# sensortag_motherboard_v005.net
KiCad netlist of a schematic drawn in EAGLE
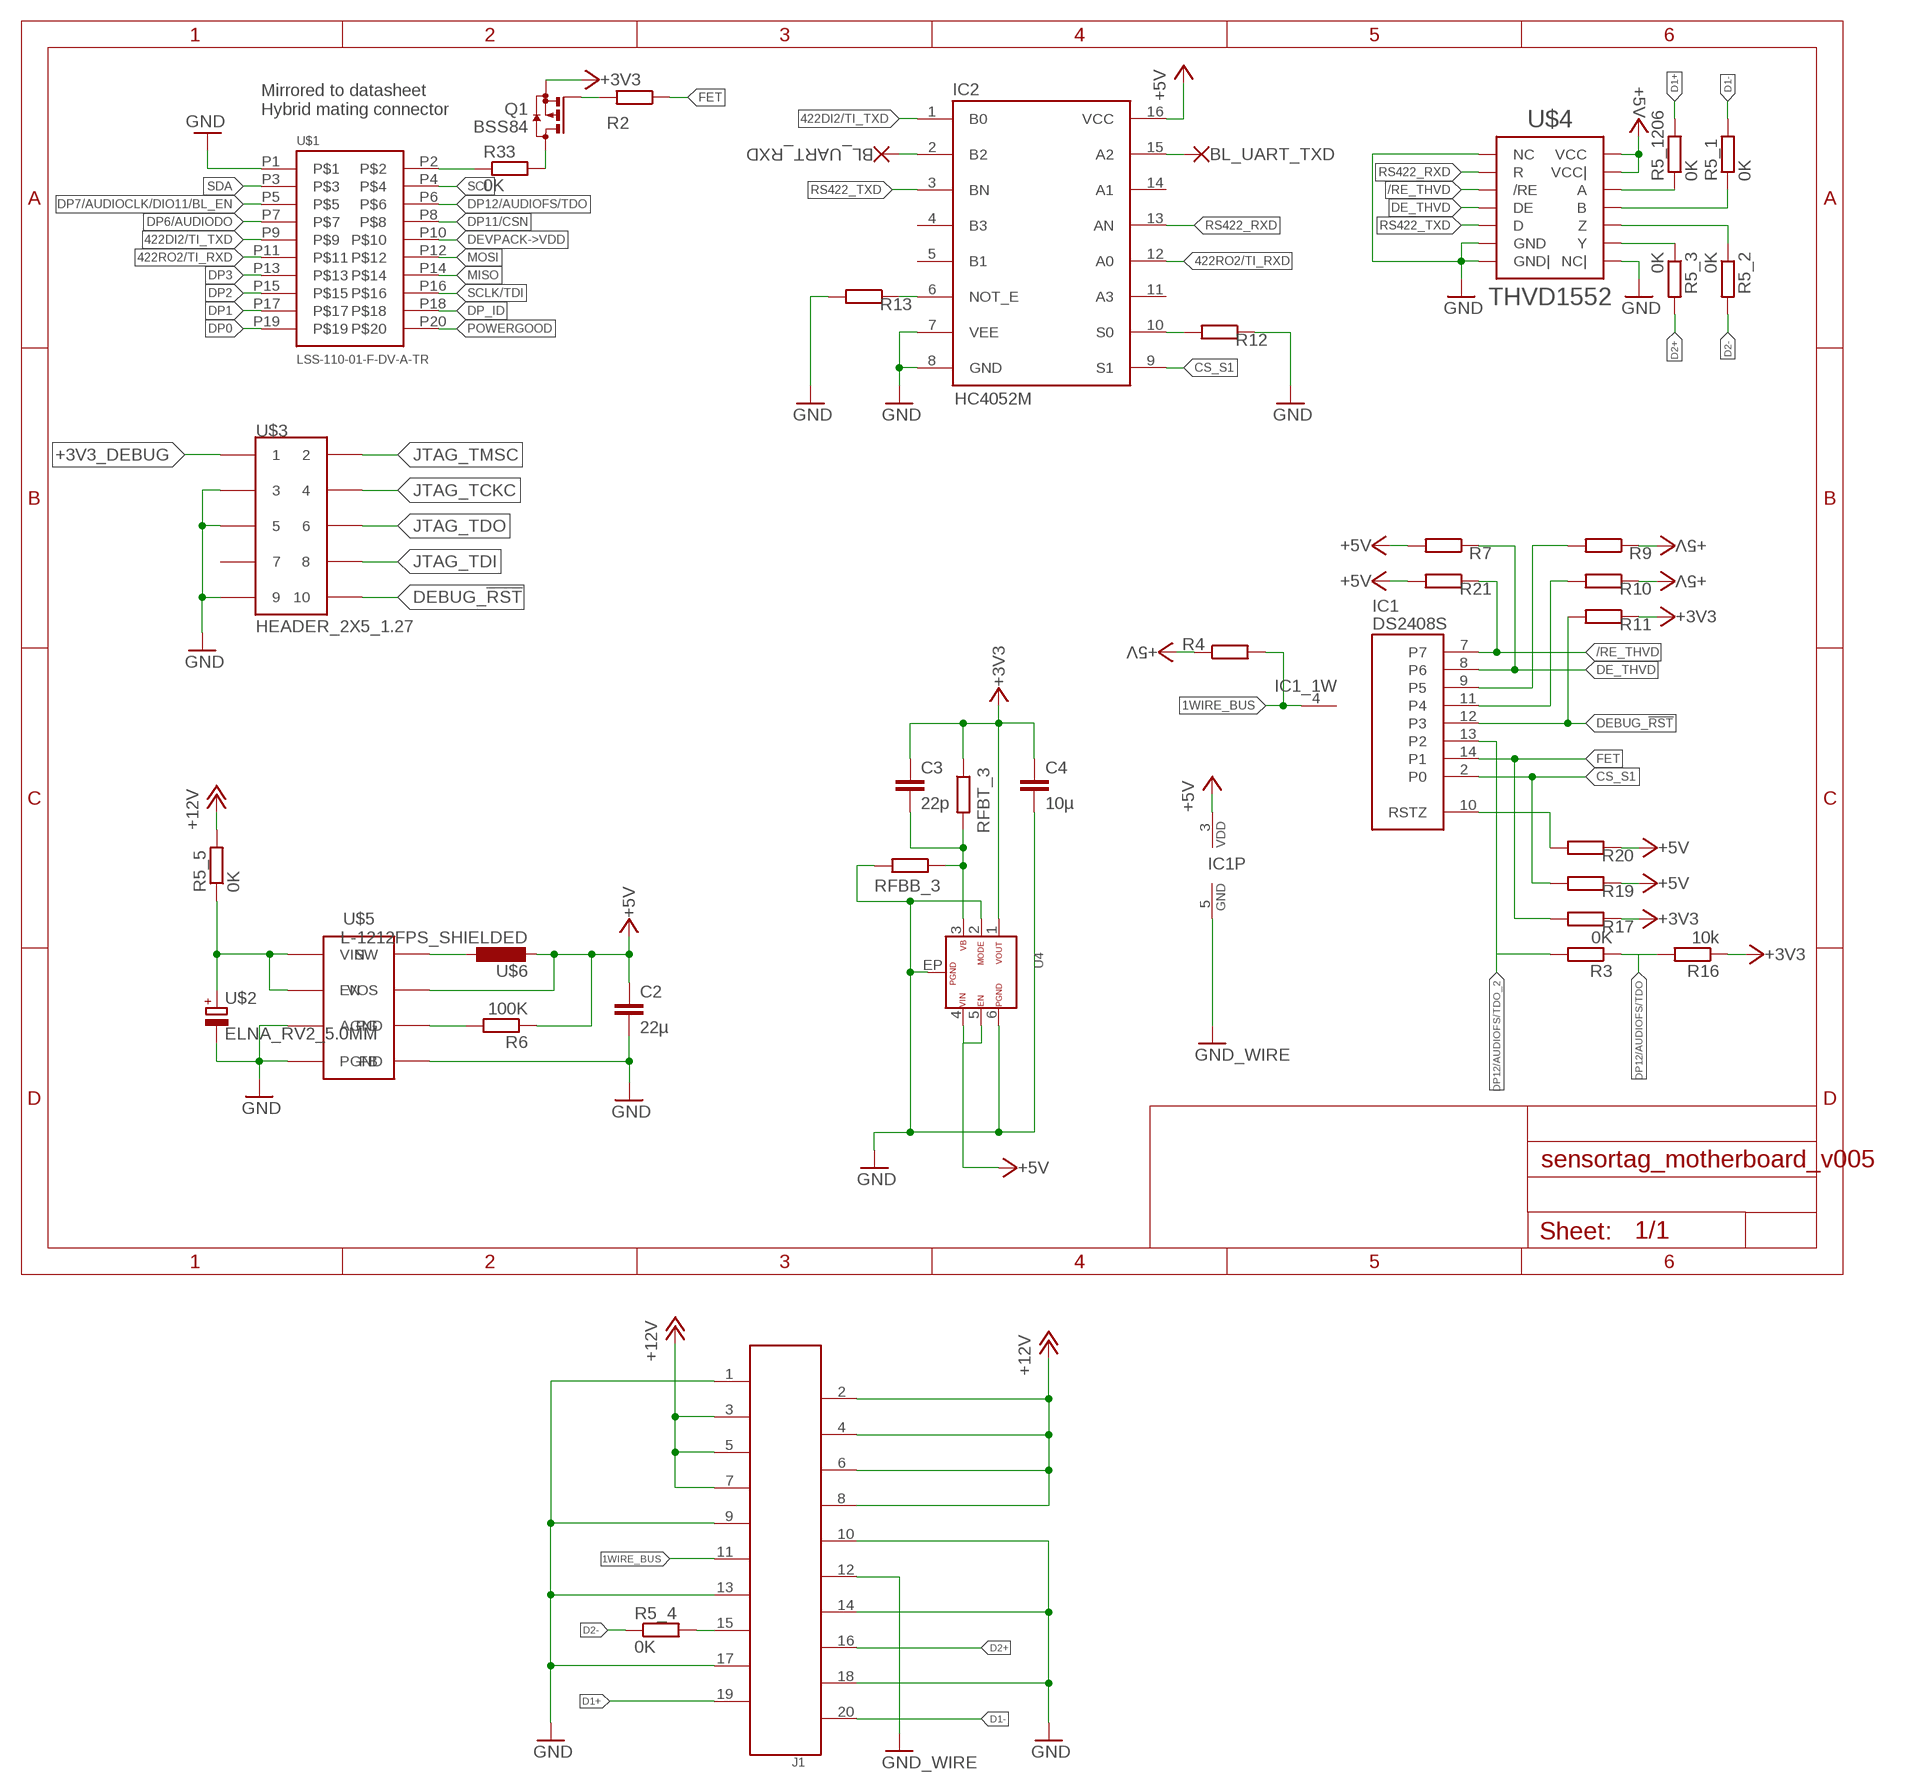
[diagram p0: schematic, sheet 1]

(export (version "E")
  (design (tool "Eeschema 10.0.6"))
  (components
    (comp (ref "BL_UART_RXD")
      (value "WIREPADSMD1,27-254")
      (footprint "eagle-import:SMD1,27-2,54")
      (libsource (lib "eagle-import") (part "WIREPADSMD1,27-254"))
    )
    (comp (ref "BL_UART_TXD")
      (value "WIREPADSMD1,27-254")
      (footprint "eagle-import:SMD1,27-2,54")
      (libsource (lib "eagle-import") (part "WIREPADSMD1,27-254"))
    )
    (comp (ref "C2")
      (value "22µ")
      (footprint "eagle-import:C1210")
      (libsource (lib "eagle-import") (part "C-EUC1210"))
    )
    (comp (ref "C3")
      (value "22p")
      (footprint "eagle-import:C0402")
      (libsource (lib "eagle-import") (part "C-EUC0402"))
    )
    (comp (ref "C4")
      (value "10µ")
      (footprint "eagle-import:C0603")
      (libsource (lib "eagle-import") (part "C-EUC0603"))
    )
    (comp (ref "IC1")
      (value "DS2408S")
      (footprint "eagle-import:SO16")
      (libsource (lib "eagle-import") (part "DS2408S"))
    )
    (comp (ref "IC2")
      (value "HC4052M")
      (footprint "eagle-import:SO16")
      (libsource (lib "eagle-import") (part "HC4052M"))
    )
    (comp (ref "J1")
      (value "490107672012")
      (footprint "eagle-import:490107672012")
      (libsource (lib "eagle-import") (part "490107672012"))
    )
    (comp (ref "Q1")
      (value "BSS84")
      (footprint "eagle-import:SOT23")
      (libsource (lib "eagle-import") (part "BSS84"))
    )
    (comp (ref "R2")
      (value "100")
      (footprint "eagle-import:R0402")
      (libsource (lib "eagle-import") (part "R0402"))
    )
    (comp (ref "R3")
      (value "0K")
      (footprint "eagle-import:R0603")
      (libsource (lib "eagle-import") (part "R-EU_R0603"))
    )
    (comp (ref "R4")
      (value "10k")
      (footprint "eagle-import:R0402")
      (libsource (lib "eagle-import") (part "R0402"))
    )
    (comp (ref "R5_1")
      (value "0K")
      (footprint "eagle-import:R1206")
      (libsource (lib "eagle-import") (part "R-EU_R1206"))
    )
    (comp (ref "R5_2")
      (value "0K")
      (footprint "eagle-import:R1206")
      (libsource (lib "eagle-import") (part "R-EU_R1206"))
    )
    (comp (ref "R5_3")
      (value "0K")
      (footprint "eagle-import:R1206")
      (libsource (lib "eagle-import") (part "R-EU_R1206"))
    )
    (comp (ref "R5_4")
      (value "0K")
      (footprint "eagle-import:R1206")
      (libsource (lib "eagle-import") (part "R-EU_R1206"))
    )
    (comp (ref "R5_5")
      (value "0K")
      (footprint "eagle-import:R1206")
      (libsource (lib "eagle-import") (part "R-EU_R1206"))
    )
    (comp (ref "R5_1206")
      (value "0K")
      (footprint "eagle-import:R1206")
      (libsource (lib "eagle-import") (part "R-EU_R1206"))
    )
    (comp (ref "R6")
      (value "100K")
      (footprint "eagle-import:R0603")
      (libsource (lib "eagle-import") (part "R-EU_R0603"))
    )
    (comp (ref "R7")
      (value "10k")
      (footprint "eagle-import:R0402")
      (libsource (lib "eagle-import") (part "R0402"))
    )
    (comp (ref "R9")
      (value "10k")
      (footprint "eagle-import:R0402")
      (libsource (lib "eagle-import") (part "R0402"))
    )
    (comp (ref "R10")
      (value "10k")
      (footprint "eagle-import:R0402")
      (libsource (lib "eagle-import") (part "R0402"))
    )
    (comp (ref "R11")
      (value "10k")
      (footprint "eagle-import:R0402")
      (libsource (lib "eagle-import") (part "R0402"))
    )
    (comp (ref "R12")
      (value "10k")
      (footprint "eagle-import:R0402")
      (libsource (lib "eagle-import") (part "R0402"))
    )
    (comp (ref "R13")
      (value "10k")
      (footprint "eagle-import:R0402")
      (libsource (lib "eagle-import") (part "R0402"))
    )
    (comp (ref "R16")
      (value "10k")
      (footprint "eagle-import:R0402")
      (libsource (lib "eagle-import") (part "R0402"))
    )
    (comp (ref "R17")
      (value "10k")
      (footprint "eagle-import:R0402")
      (libsource (lib "eagle-import") (part "R0402"))
    )
    (comp (ref "R19")
      (value "10k")
      (footprint "eagle-import:R0402")
      (libsource (lib "eagle-import") (part "R0402"))
    )
    (comp (ref "R20")
      (value "10k")
      (footprint "eagle-import:R0402")
      (libsource (lib "eagle-import") (part "R0402"))
    )
    (comp (ref "R21")
      (value "10k")
      (footprint "eagle-import:R0402")
      (libsource (lib "eagle-import") (part "R0402"))
    )
    (comp (ref "R33")
      (value "0K")
      (footprint "eagle-import:R0603")
      (libsource (lib "eagle-import") (part "R-EU_R0603"))
    )
    (comp (ref "RFBB_3")
      (value "22,1K")
      (footprint "eagle-import:R0402")
      (libsource (lib "eagle-import") (part "R0402"))
    )
    (comp (ref "RFBT_3")
      (value "100K")
      (footprint "eagle-import:R0402")
      (libsource (lib "eagle-import") (part "R0402"))
    )
    (comp (ref "U$1")
      (value "LSS-110-01-F-DV-A-TR")
      (footprint "eagle-import:LSS-110-01-F-DV-A-TR")
      (libsource (lib "eagle-import") (part "LSS-110-01-F-DV-A-TR"))
    )
    (comp (ref "U$2")
      (value "ELNA_RV2_5.0MM")
      (footprint "eagle-import:ELNA_RV2_5.0MM")
      (libsource (lib "eagle-import") (part "ELNA_RV2_5.0MM"))
    )
    (comp (ref "U$3")
      (value "HEADER_2X5_1.27")
      (footprint "eagle-import:HEADER_2X5_1.27")
      (libsource (lib "eagle-import") (part "HEADER_2X5_1.27"))
    )
    (comp (ref "U$4")
      (value "TVHD1552")
      (footprint "eagle-import:SO14")
      (libsource (lib "eagle-import") (part "TVHD1552"))
    )
    (comp (ref "U$5")
      (value "TPS62173")
      (footprint "eagle-import:WSON8")
      (libsource (lib "eagle-import") (part "TPS62173"))
    )
    (comp (ref "U$6")
      (value "L-1212FPS_SHIELDED")
      (footprint "eagle-import:L-1212FPS_SHIELDED")
      (libsource (lib "eagle-import") (part "L-1212FPS_SHIELDED"))
    )
    (comp (ref "U4")
      (value "VDMM_171960501")
      (footprint "eagle-import:VDMM_171960501")
      (libsource (lib "eagle-import") (part "VDMM_171960501"))
    )
  )
  (nets
    (net (code "1") (name "+3V3") (class "Default")
      (node (ref "C3") (pin "1") (pinfunction "1_1") (pintype "passive"))
      (node (ref "C4") (pin "1") (pinfunction "1_1") (pintype "passive"))
      (node (ref "Q1") (pin "2") (pinfunction "S_2") (pintype "passive"))
      (node (ref "R11") (pin "P$1") (pinfunction "1_P$1") (pintype "passive"))
      (node (ref "R16") (pin "P$1") (pinfunction "1_P$1") (pintype "passive"))
      (node (ref "R17") (pin "P$1") (pinfunction "1_P$1") (pintype "passive"))
      (node (ref "RFBT_3") (pin "P$1") (pinfunction "1_P$1") (pintype "passive"))
      (node (ref "U4") (pin "1") (pinfunction "VOUT_1") (pintype "output"))
    )
    (net (code "2") (name "+3V3_DEBUG") (class "Default")
      (node (ref "U$3") (pin "P$1") (pinfunction "1_P$1") (pintype "bidirectional"))
    )
    (net (code "3") (name "+5V") (class "Default")
      (node (ref "C2") (pin "1") (pinfunction "1_1") (pintype "passive"))
      (node (ref "IC1") (pin "3") (pinfunction "VDD_3") (pintype "power_in"))
      (node (ref "IC2") (pin "16") (pinfunction "VCC_16") (pintype "bidirectional"))
      (node (ref "R10") (pin "P$1") (pinfunction "1_P$1") (pintype "passive"))
      (node (ref "R19") (pin "P$1") (pinfunction "1_P$1") (pintype "passive"))
      (node (ref "R20") (pin "P$1") (pinfunction "1_P$1") (pintype "passive"))
      (node (ref "R21") (pin "P$2") (pinfunction "2_P$2") (pintype "passive"))
      (node (ref "R4") (pin "P$1") (pinfunction "1_P$1") (pintype "passive"))
      (node (ref "R6") (pin "1") (pinfunction "1_1") (pintype "passive"))
      (node (ref "R7") (pin "P$2") (pinfunction "2_P$2") (pintype "passive"))
      (node (ref "R9") (pin "P$1") (pinfunction "1_P$1") (pintype "passive"))
      (node (ref "U$4") (pin "13") (pinfunction "VCC|_13") (pintype "bidirectional"))
      (node (ref "U$4") (pin "14") (pinfunction "VCC_14") (pintype "bidirectional"))
      (node (ref "U$5") (pin "VOS") (pinfunction "VOS_VOS") (pintype "bidirectional"))
      (node (ref "U$6") (pin "P$2") (pinfunction "2_P$2") (pintype "passive"))
      (node (ref "U4") (pin "4") (pinfunction "VIN_4") (pintype "input"))
      (node (ref "U4") (pin "5") (pinfunction "EN_5") (pintype "bidirectional"))
    )
    (net (code "4") (name "+12V") (class "Default")
      (node (ref "J1") (pin "2") (pinfunction "19_2") (pintype "passive"))
      (node (ref "J1") (pin "3") (pinfunction "18_3") (pintype "passive"))
      (node (ref "J1") (pin "4") (pinfunction "17_4") (pintype "passive"))
      (node (ref "J1") (pin "5") (pinfunction "16_5") (pintype "passive"))
      (node (ref "J1") (pin "6") (pinfunction "15_6") (pintype "passive"))
      (node (ref "J1") (pin "7") (pinfunction "14_7") (pintype "passive"))
      (node (ref "J1") (pin "8") (pinfunction "13_8") (pintype "passive"))
      (node (ref "R5_5") (pin "2") (pinfunction "2_2") (pintype "passive"))
    )
    (net (code "5") (name "/DEBUG_~{RST}") (class "Default")
      (node (ref "IC1") (pin "12") (pinfunction "P3_12") (pintype "open_collector"))
      (node (ref "R11") (pin "P$2") (pinfunction "2_P$2") (pintype "passive"))
      (node (ref "U$3") (pin "P$10") (pinfunction "10_P$10") (pintype "bidirectional"))
    )
    (net (code "6") (name "1WIRE_BUS") (class "Default")
      (node (ref "IC1") (pin "4") (pinfunction "1W_4") (pintype "power_in"))
      (node (ref "J1") (pin "11") (pinfunction "10_11") (pintype "passive"))
      (node (ref "R4") (pin "P$2") (pinfunction "2_P$2") (pintype "passive"))
    )
    (net (code "7") (name "422DI2{slash}TI_TXD") (class "Default")
      (node (ref "IC2") (pin "1") (pinfunction "B0_1") (pintype "bidirectional"))
      (node (ref "U$1") (pin "P9") (pinfunction "P$9_P9") (pintype "bidirectional"))
    )
    (net (code "8") (name "422RO2{slash}TI_RXD") (class "Default")
      (node (ref "IC2") (pin "12") (pinfunction "A0_12") (pintype "bidirectional"))
      (node (ref "U$1") (pin "P11") (pinfunction "P$11_P11") (pintype "bidirectional"))
    )
    (net (code "9") (name "CS_S1") (class "Default")
      (node (ref "IC1") (pin "2") (pinfunction "P0_2") (pintype "open_collector"))
      (node (ref "IC2") (pin "9") (pinfunction "S1_9") (pintype "bidirectional"))
      (node (ref "R19") (pin "P$2") (pinfunction "2_P$2") (pintype "passive"))
    )
    (net (code "10") (name "D1+") (class "Default")
      (node (ref "J1") (pin "19") (pinfunction "2_19") (pintype "passive"))
      (node (ref "R5_1206") (pin "2") (pinfunction "2_2") (pintype "passive"))
    )
    (net (code "11") (name "D1-") (class "Default")
      (node (ref "J1") (pin "20") (pinfunction "1_20") (pintype "passive"))
      (node (ref "R5_1") (pin "2") (pinfunction "2_2") (pintype "passive"))
    )
    (net (code "12") (name "D2+") (class "Default")
      (node (ref "J1") (pin "16") (pinfunction "5_16") (pintype "passive"))
      (node (ref "R5_3") (pin "2") (pinfunction "2_2") (pintype "passive"))
    )
    (net (code "13") (name "D2-") (class "Default")
      (node (ref "R5_2") (pin "2") (pinfunction "2_2") (pintype "passive"))
      (node (ref "R5_4") (pin "1") (pinfunction "1_1") (pintype "passive"))
    )
    (net (code "14") (name "DEVPACK->VDD") (class "Default")
      (node (ref "U$1") (pin "P10") (pinfunction "P$10_P10") (pintype "bidirectional"))
    )
    (net (code "15") (name "DE_THVD") (class "Default")
      (node (ref "IC1") (pin "8") (pinfunction "P6_8") (pintype "open_collector"))
      (node (ref "R7") (pin "P$1") (pinfunction "1_P$1") (pintype "passive"))
      (node (ref "U$4") (pin "4") (pinfunction "DE_4") (pintype "bidirectional"))
    )
    (net (code "16") (name "DP0") (class "Default")
      (node (ref "U$1") (pin "P19") (pinfunction "P$19_P19") (pintype "bidirectional"))
    )
    (net (code "17") (name "DP1") (class "Default")
      (node (ref "U$1") (pin "P17") (pinfunction "P$17_P17") (pintype "bidirectional"))
    )
    (net (code "18") (name "DP2") (class "Default")
      (node (ref "U$1") (pin "P15") (pinfunction "P$15_P15") (pintype "bidirectional"))
    )
    (net (code "19") (name "DP3") (class "Default")
      (node (ref "U$1") (pin "P13") (pinfunction "P$13_P13") (pintype "bidirectional"))
    )
    (net (code "20") (name "DP6{slash}AUDIODO") (class "Default")
      (node (ref "U$1") (pin "P7") (pinfunction "P$7_P7") (pintype "bidirectional"))
    )
    (net (code "21") (name "DP7{slash}AUDIOCLK{slash}DIO11{slash}BL_EN") (class "Default")
      (node (ref "U$1") (pin "P5") (pinfunction "P$5_P5") (pintype "bidirectional"))
    )
    (net (code "22") (name "DP11{slash}CSN") (class "Default")
      (node (ref "U$1") (pin "P8") (pinfunction "P$8_P8") (pintype "bidirectional"))
    )
    (net (code "23") (name "DP12{slash}AUDIOFS{slash}TDO") (class "Default")
      (node (ref "R16") (pin "P$2") (pinfunction "2_P$2") (pintype "passive"))
      (node (ref "R3") (pin "1") (pinfunction "1_1") (pintype "passive"))
      (node (ref "U$1") (pin "P6") (pinfunction "P$6_P6") (pintype "bidirectional"))
    )
    (net (code "24") (name "DP12{slash}AUDIOFS{slash}TDO_2") (class "Default")
      (node (ref "IC1") (pin "13") (pinfunction "P2_13") (pintype "open_collector"))
      (node (ref "R3") (pin "2") (pinfunction "2_2") (pintype "passive"))
    )
    (net (code "25") (name "DP_ID") (class "Default")
      (node (ref "U$1") (pin "P18") (pinfunction "P$18_P18") (pintype "bidirectional"))
    )
    (net (code "26") (name "FET") (class "Default")
      (node (ref "IC1") (pin "14") (pinfunction "P1_14") (pintype "open_collector"))
      (node (ref "R17") (pin "P$2") (pinfunction "2_P$2") (pintype "passive"))
      (node (ref "R2") (pin "P$1") (pinfunction "1_P$1") (pintype "passive"))
    )
    (net (code "27") (name "GND") (class "Default")
      (node (ref "C2") (pin "2") (pinfunction "2_2") (pintype "passive"))
      (node (ref "C4") (pin "2") (pinfunction "2_2") (pintype "passive"))
      (node (ref "IC2") (pin "7") (pinfunction "VEE_7") (pintype "bidirectional"))
      (node (ref "IC2") (pin "8") (pinfunction "GND_8") (pintype "bidirectional"))
      (node (ref "J1") (pin "1") (pinfunction "20_1") (pintype "passive"))
      (node (ref "J1") (pin "10") (pinfunction "11_10") (pintype "passive"))
      (node (ref "J1") (pin "13") (pinfunction "8_13") (pintype "passive"))
      (node (ref "J1") (pin "14") (pinfunction "7_14") (pintype "passive"))
      (node (ref "J1") (pin "17") (pinfunction "4_17") (pintype "passive"))
      (node (ref "J1") (pin "18") (pinfunction "3_18") (pintype "passive"))
      (node (ref "J1") (pin "9") (pinfunction "12_9") (pintype "passive"))
      (node (ref "R12") (pin "P$1") (pinfunction "1_P$1") (pintype "passive"))
      (node (ref "R13") (pin "P$2") (pinfunction "2_P$2") (pintype "passive"))
      (node (ref "RFBB_3") (pin "P$2") (pinfunction "2_P$2") (pintype "passive"))
      (node (ref "U$1") (pin "P1") (pinfunction "P$1_P1") (pintype "bidirectional"))
      (node (ref "U$2") (pin "P-") (pinfunction "-_P-") (pintype "passive"))
      (node (ref "U$3") (pin "P$3") (pinfunction "3_P$3") (pintype "bidirectional"))
      (node (ref "U$3") (pin "P$5") (pinfunction "5_P$5") (pintype "bidirectional"))
      (node (ref "U$3") (pin "P$9") (pinfunction "9_P$9") (pintype "bidirectional"))
      (node (ref "U$4") (pin "1") (pinfunction "NC_1") (pintype "bidirectional"))
      (node (ref "U$4") (pin "6") (pinfunction "GND_6") (pintype "bidirectional"))
      (node (ref "U$4") (pin "7") (pinfunction "GND|_7") (pintype "bidirectional"))
      (node (ref "U$4") (pin "8") (pinfunction "NC|_8") (pintype "bidirectional"))
      (node (ref "U$5") (pin "AGND") (pinfunction "AGND_AGND") (pintype "bidirectional"))
      (node (ref "U$5") (pin "AGND2") (pinfunction "AGND_AGND2") (pintype "bidirectional"))
      (node (ref "U$5") (pin "FB") (pinfunction "FB_FB") (pintype "bidirectional"))
      (node (ref "U$5") (pin "PGND") (pinfunction "PGND_PGND") (pintype "bidirectional"))
      (node (ref "U4") (pin "2") (pinfunction "MODE_2") (pintype "bidirectional"))
      (node (ref "U4") (pin "6") (pinfunction "PGND_6") (pintype "bidirectional"))
      (node (ref "U4") (pin "EP") (pinfunction "PGND1_EP") (pintype "bidirectional"))
    )
    (net (code "28") (name "GND_WIRE") (class "Default")
      (node (ref "IC1") (pin "5") (pinfunction "GND_5") (pintype "power_in"))
      (node (ref "J1") (pin "12") (pinfunction "9_12") (pintype "passive"))
    )
    (net (code "29") (name "JTAG_TCKC") (class "Default")
      (node (ref "U$3") (pin "P$4") (pinfunction "4_P$4") (pintype "bidirectional"))
    )
    (net (code "30") (name "JTAG_TDI") (class "Default")
      (node (ref "U$3") (pin "P$8") (pinfunction "8_P$8") (pintype "bidirectional"))
    )
    (net (code "31") (name "JTAG_TDO") (class "Default")
      (node (ref "U$3") (pin "P$6") (pinfunction "6_P$6") (pintype "bidirectional"))
    )
    (net (code "32") (name "JTAG_TMSC") (class "Default")
      (node (ref "U$3") (pin "P$2") (pinfunction "2_P$2") (pintype "bidirectional"))
    )
    (net (code "33") (name "MISO") (class "Default")
      (node (ref "U$1") (pin "P14") (pinfunction "P$14_P14") (pintype "bidirectional"))
    )
    (net (code "34") (name "MOSI") (class "Default")
      (node (ref "U$1") (pin "P12") (pinfunction "P$12_P12") (pintype "bidirectional"))
    )
    (net (code "35") (name "Net-(BL_UART_RXD-P)") (class "Default")
      (node (ref "BL_UART_RXD") (pin "1") (pinfunction "P_1") (pintype "passive"))
      (node (ref "IC2") (pin "2") (pinfunction "B2_2") (pintype "bidirectional"))
    )
    (net (code "36") (name "Net-(BL_UART_TXD-P)") (class "Default")
      (node (ref "BL_UART_TXD") (pin "1") (pinfunction "P_1") (pintype "passive"))
      (node (ref "IC2") (pin "15") (pinfunction "A2_15") (pintype "bidirectional"))
    )
    (net (code "37") (name "Net-(IC1A-P4)") (class "Default")
      (node (ref "IC1") (pin "11") (pinfunction "P4_11") (pintype "open_collector"))
      (node (ref "R10") (pin "P$2") (pinfunction "2_P$2") (pintype "passive"))
    )
    (net (code "38") (name "Net-(IC1A-P5)") (class "Default")
      (node (ref "IC1") (pin "9") (pinfunction "P5_9") (pintype "open_collector"))
      (node (ref "R9") (pin "P$2") (pinfunction "2_P$2") (pintype "passive"))
    )
    (net (code "39") (name "Net-(IC1A-RSTZ)") (class "Default")
      (node (ref "IC1") (pin "10") (pinfunction "RSTZ_10") (pintype "open_collector"))
      (node (ref "R20") (pin "P$2") (pinfunction "2_P$2") (pintype "passive"))
    )
    (net (code "40") (name "Net-(IC2-NOT_E)") (class "Default")
      (node (ref "IC2") (pin "6") (pinfunction "NOT_E_6") (pintype "bidirectional"))
      (node (ref "R13") (pin "P$1") (pinfunction "1_P$1") (pintype "passive"))
    )
    (net (code "41") (name "Net-(IC2-S0)") (class "Default")
      (node (ref "IC2") (pin "10") (pinfunction "S0_10") (pintype "bidirectional"))
      (node (ref "R12") (pin "P$2") (pinfunction "2_P$2") (pintype "passive"))
    )
    (net (code "42") (name "Net-(J1-6)") (class "Default")
      (node (ref "J1") (pin "15") (pinfunction "6_15") (pintype "passive"))
      (node (ref "R5_4") (pin "2") (pinfunction "2_2") (pintype "passive"))
    )
    (net (code "43") (name "Net-(Q1-D)") (class "Default")
      (node (ref "Q1") (pin "3") (pinfunction "D_3") (pintype "passive"))
      (node (ref "R33") (pin "2") (pinfunction "2_2") (pintype "passive"))
    )
    (net (code "44") (name "Net-(Q1-G)") (class "Default")
      (node (ref "Q1") (pin "1") (pinfunction "G_1") (pintype "passive"))
      (node (ref "R2") (pin "P$2") (pinfunction "2_P$2") (pintype "passive"))
    )
    (net (code "45") (name "Net-(R6-Pad2)") (class "Default")
      (node (ref "R6") (pin "2") (pinfunction "2_2") (pintype "passive"))
      (node (ref "U$5") (pin "PG") (pinfunction "PG_PG") (pintype "bidirectional"))
    )
    (net (code "46") (name "Net-(RFBB_3-1)") (class "Default")
      (node (ref "C3") (pin "2") (pinfunction "2_2") (pintype "passive"))
      (node (ref "RFBB_3") (pin "P$1") (pinfunction "1_P$1") (pintype "passive"))
      (node (ref "RFBT_3") (pin "P$2") (pinfunction "2_P$2") (pintype "passive"))
      (node (ref "U4") (pin "3") (pinfunction "FB_3") (pintype "bidirectional"))
    )
    (net (code "47") (name "Net-(U$1-P$2)") (class "Default")
      (node (ref "R33") (pin "1") (pinfunction "1_1") (pintype "passive"))
      (node (ref "U$1") (pin "P2") (pinfunction "P$2_P2") (pintype "bidirectional"))
    )
    (net (code "48") (name "Net-(U$2-+)") (class "Default")
      (node (ref "R5_5") (pin "1") (pinfunction "1_1") (pintype "passive"))
      (node (ref "U$2") (pin "P+") (pinfunction "+_P+") (pintype "passive"))
      (node (ref "U$5") (pin "EN") (pinfunction "EN_EN") (pintype "bidirectional"))
      (node (ref "U$5") (pin "VIN") (pinfunction "VIN_VIN") (pintype "bidirectional"))
    )
    (net (code "49") (name "Net-(U$4-A)") (class "Default")
      (node (ref "R5_1206") (pin "1") (pinfunction "1_1") (pintype "passive"))
      (node (ref "U$4") (pin "12") (pinfunction "A_12") (pintype "bidirectional"))
    )
    (net (code "50") (name "Net-(U$4-B)") (class "Default")
      (node (ref "R5_1") (pin "1") (pinfunction "1_1") (pintype "passive"))
      (node (ref "U$4") (pin "11") (pinfunction "B_11") (pintype "bidirectional"))
    )
    (net (code "51") (name "Net-(U$4-Y)") (class "Default")
      (node (ref "R5_3") (pin "1") (pinfunction "1_1") (pintype "passive"))
      (node (ref "U$4") (pin "9") (pinfunction "Y_9") (pintype "bidirectional"))
    )
    (net (code "52") (name "Net-(U$4-Z)") (class "Default")
      (node (ref "R5_2") (pin "1") (pinfunction "1_1") (pintype "passive"))
      (node (ref "U$4") (pin "10") (pinfunction "Z_10") (pintype "bidirectional"))
    )
    (net (code "53") (name "Net-(U$6-1)") (class "Default")
      (node (ref "U$5") (pin "SW") (pinfunction "SW_SW") (pintype "bidirectional"))
      (node (ref "U$6") (pin "P$1") (pinfunction "1_P$1") (pintype "passive"))
    )
    (net (code "54") (name "POWERGOOD") (class "Default")
      (node (ref "U$1") (pin "P20") (pinfunction "P$20_P20") (pintype "bidirectional"))
    )
    (net (code "55") (name "RS422_RXD") (class "Default")
      (node (ref "IC2") (pin "13") (pinfunction "AN_13") (pintype "bidirectional"))
      (node (ref "U$4") (pin "2") (pinfunction "R_2") (pintype "bidirectional"))
    )
    (net (code "56") (name "RS422_TXD") (class "Default")
      (node (ref "IC2") (pin "3") (pinfunction "BN_3") (pintype "bidirectional"))
      (node (ref "U$4") (pin "5") (pinfunction "D_5") (pintype "bidirectional"))
    )
    (net (code "57") (name "SCL") (class "Default")
      (node (ref "U$1") (pin "P4") (pinfunction "P$4_P4") (pintype "bidirectional"))
    )
    (net (code "58") (name "SCLK{slash}TDI") (class "Default")
      (node (ref "U$1") (pin "P16") (pinfunction "P$16_P16") (pintype "bidirectional"))
    )
    (net (code "59") (name "SDA") (class "Default")
      (node (ref "U$1") (pin "P3") (pinfunction "P$3_P3") (pintype "bidirectional"))
    )
    (net (code "60") (name "unconnected-(IC2-A1-Pad14)") (class "Default")
      (node (ref "IC2") (pin "14") (pinfunction "A1_14") (pintype "bidirectional"))
    )
    (net (code "61") (name "unconnected-(IC2-A3-Pad11)") (class "Default")
      (node (ref "IC2") (pin "11") (pinfunction "A3_11") (pintype "bidirectional"))
    )
    (net (code "62") (name "unconnected-(IC2-B1-Pad5)") (class "Default")
      (node (ref "IC2") (pin "5") (pinfunction "B1_5") (pintype "bidirectional"))
    )
    (net (code "63") (name "unconnected-(IC2-B3-Pad4)") (class "Default")
      (node (ref "IC2") (pin "4") (pinfunction "B3_4") (pintype "bidirectional"))
    )
    (net (code "64") (name "unconnected-(U$3-7-PadP$7)") (class "Default")
      (node (ref "U$3") (pin "P$7") (pinfunction "7_P$7") (pintype "bidirectional"))
    )
    (net (code "65") (name "{slash}RE_THVD") (class "Default")
      (node (ref "IC1") (pin "7") (pinfunction "P7_7") (pintype "open_collector"))
      (node (ref "R21") (pin "P$1") (pinfunction "1_P$1") (pintype "passive"))
      (node (ref "U$4") (pin "3") (pinfunction "/RE_3") (pintype "bidirectional"))
    )
  )
)
